# LConnector.net
KiCad netlist of a schematic drawn in EAGLE
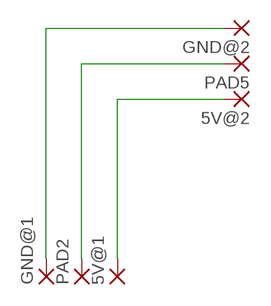
[diagram p0: schematic, sheet 1]

(export (version "E")
  (design (tool "Eeschema 10.0.6"))
  (components
    (comp (ref "5V@1")
      (value "SMD2")
      (footprint "eagle-import:SMD1,27-2,54")
      (libsource (lib "eagle-import") (part "SMD2"))
    )
    (comp (ref "5V@2")
      (value "SMD2")
      (footprint "eagle-import:SMD1,27-2,54")
      (libsource (lib "eagle-import") (part "SMD2"))
    )
    (comp (ref "GND@1")
      (value "SMD2")
      (footprint "eagle-import:SMD1,27-2,54")
      (libsource (lib "eagle-import") (part "SMD2"))
    )
    (comp (ref "GND@2")
      (value "SMD2")
      (footprint "eagle-import:SMD1,27-2,54")
      (libsource (lib "eagle-import") (part "SMD2"))
    )
    (comp (ref "PAD2")
      (value "SMD2")
      (footprint "eagle-import:SMD1,27-2,54")
      (libsource (lib "eagle-import") (part "SMD2"))
    )
    (comp (ref "PAD5")
      (value "SMD2")
      (footprint "eagle-import:SMD1,27-2,54")
      (libsource (lib "eagle-import") (part "SMD2"))
    )
  )
  (nets
    (net (code "1") (name "Net-(5V@1-P)") (class "Default")
      (node (ref "5V@1") (pin "1") (pinfunction "P_1") (pintype "passive"))
      (node (ref "5V@2") (pin "1") (pinfunction "P_1") (pintype "passive"))
    )
    (net (code "2") (name "Net-(GND@1-P)") (class "Default")
      (node (ref "GND@1") (pin "1") (pinfunction "P_1") (pintype "passive"))
      (node (ref "GND@2") (pin "1") (pinfunction "P_1") (pintype "passive"))
    )
    (net (code "3") (name "Net-(PAD2-P)") (class "Default")
      (node (ref "PAD2") (pin "1") (pinfunction "P_1") (pintype "passive"))
      (node (ref "PAD5") (pin "1") (pinfunction "P_1") (pintype "passive"))
    )
  )
)
